# DebugUSB.net
KiCad netlist of a schematic drawn in Altium Designer
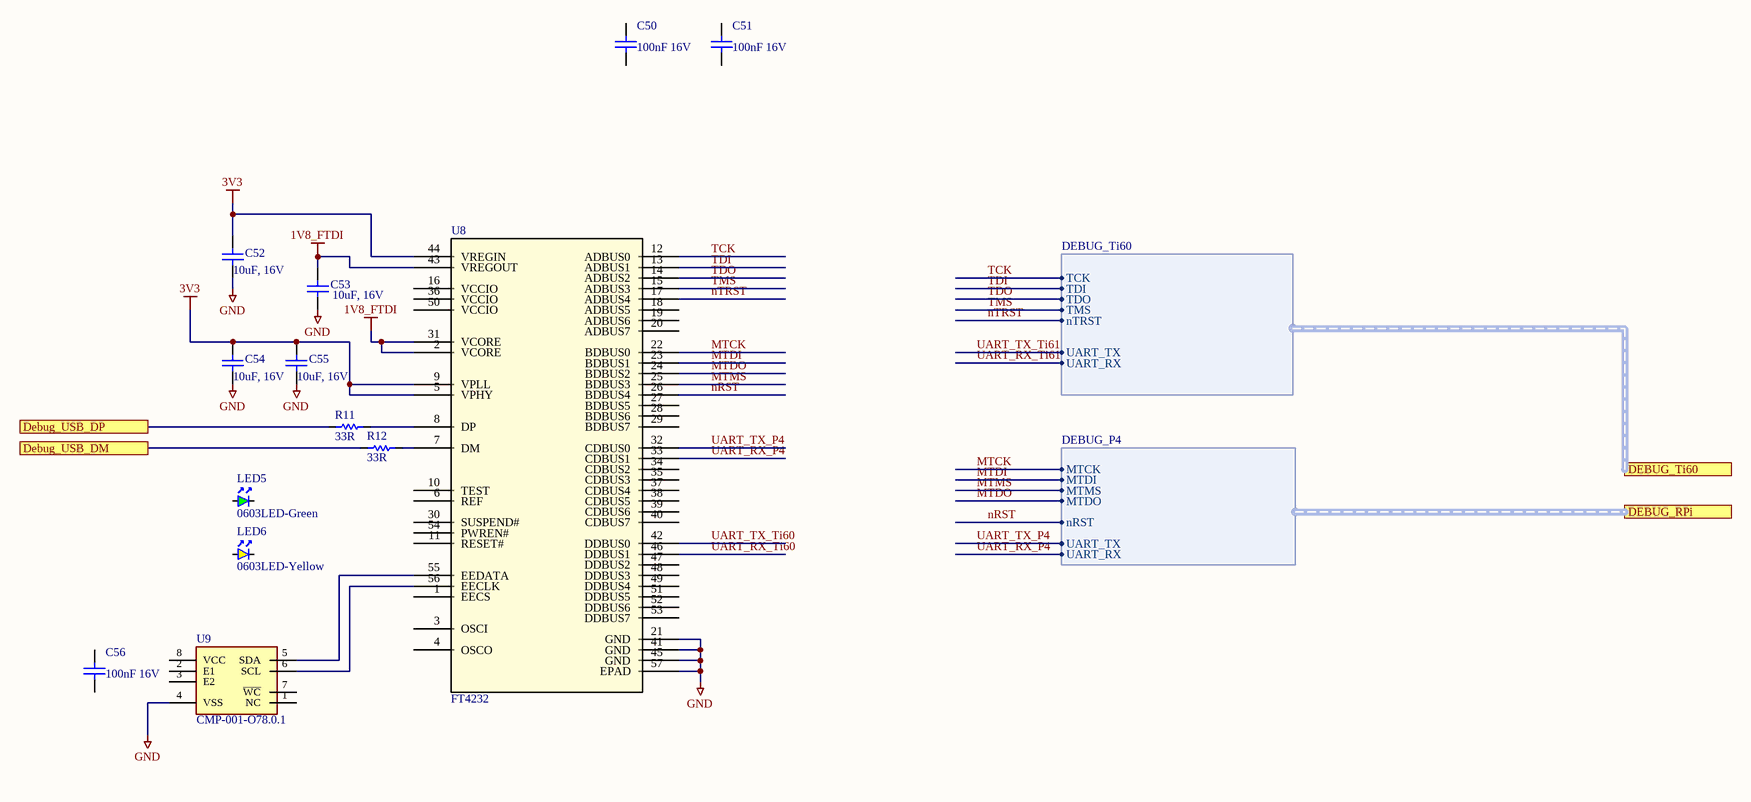
[diagram p0: DebugUSB.SchDoc]

(export (version "E")
  (design (tool "Eeschema 10.0.6"))
  (components
    (comp (ref "C50") (value "100nF 16V") (footprint "0402") (libsource (lib "Revolve NTNU") (part "CAP")))
    (comp (ref "C51") (value "100nF 16V") (footprint "0402") (libsource (lib "Revolve NTNU") (part "CAP")))
    (comp (ref "C52")
      (value "10uF, 16V")
      (footprint "0603 Capacitor")
      (description "10uF, 16V, 20%, X5R, 0603")
      (libsource (lib "Revolve NTNU") (part "CAP"))
    )
    (comp (ref "C53")
      (value "10uF, 16V")
      (footprint "0603 Capacitor")
      (description "10uF, 16V, 20%, X5R, 0603")
      (libsource (lib "Revolve NTNU") (part "CAP"))
    )
    (comp (ref "C54")
      (value "10uF, 16V")
      (footprint "0603 Capacitor")
      (description "10uF, 16V, 20%, X5R, 0603")
      (libsource (lib "Revolve NTNU") (part "CAP"))
    )
    (comp (ref "C55")
      (value "10uF, 16V")
      (footprint "0603 Capacitor")
      (description "10uF, 16V, 20%, X5R, 0603")
      (libsource (lib "Revolve NTNU") (part "CAP"))
    )
    (comp (ref "C56") (value "100nF 16V") (footprint "0402") (libsource (lib "Revolve NTNU") (part "CAP")))
    (comp (ref "LED5")
      (value "0603LED-Green")
      (footprint "LED-0603-RED")
      (description "SMD LED 0603, Green")
      (libsource (lib "Revolve NTNU") (part "LED"))
    )
    (comp (ref "LED6")
      (value "0603LED-Yellow")
      (footprint "LED-0603-RED")
      (description "SMD LED 0603, Yellow")
      (libsource (lib "Revolve NTNU") (part "LED"))
    )
    (comp (ref "R11")
      (value "33R")
      (footprint "0603 Resistor")
      (description "33R, 1%, 1/10W, 0603")
      (fields (field (name "TOLERANCE") "1%") (field (name "MANUFACTURER") "Panasonic"))
      (libsource (lib "Revolve NTNU") (part "Resistor"))
    )
    (comp (ref "R12")
      (value "33R")
      (footprint "0603 Resistor")
      (description "33R, 1%, 1/10W, 0603")
      (fields (field (name "TOLERANCE") "1%") (field (name "MANUFACTURER") "Panasonic"))
      (libsource (lib "Revolve NTNU") (part "Resistor"))
    )
    (comp (ref "U8")
      (value "FT4232")
      (footprint "VQFN-56Y856_FTD-M")
      (description "Usb Hi-speed to Quad Channel Serial UART/JTAG/SPI/I2C IC, QFN-56")
      (libsource (lib "Eirik Silnes") (part "FT4232H-56Q-REEL"))
    )
    (comp (ref "U9")
      (value "CMP-001-O78.0.1")
      (footprint "M24C04-DRMN3TP_K-Footprint-1")
      (description "IC EEPROM 4KBIT I2C 1MHZ 8SOIC")
      (fields
        (field (name "MANUFACTURER PART NUMBER") "M24C04-DRMN3TP/K")
        (field (name "MANUFACTURER") "STMicroelectronics")
      )
      (libsource (lib "Eirik Silnes") (part "CMP-001-O78.0.1"))
    )
  )
  (nets
    (net (code "3") (name "/Debug_USB_DM") (class "Default")
      (node (ref "R12") (pin "1") (pinfunction "1_1") (pintype "passive"))
    )
    (net (code "4") (name "/Debug_USB_DP") (class "Default")
      (node (ref "R11") (pin "1") (pinfunction "1_1") (pintype "passive"))
    )
    (net (code "5") (name "/MTCK") (class "Default")
      (node (ref "U8") (pin "22") (pinfunction "BDBUS0_22") (pintype "passive"))
    )
    (net (code "6") (name "/MTDI") (class "Default")
      (node (ref "U8") (pin "23") (pinfunction "BDBUS1_23") (pintype "passive"))
    )
    (net (code "7") (name "/MTDO") (class "Default")
      (node (ref "U8") (pin "24") (pinfunction "BDBUS2_24") (pintype "passive"))
    )
    (net (code "8") (name "/MTMS") (class "Default")
      (node (ref "U8") (pin "25") (pinfunction "BDBUS3_25") (pintype "passive"))
    )
    (net (code "9") (name "/TCK") (class "Default")
      (node (ref "U8") (pin "12") (pinfunction "ADBUS0_12") (pintype "passive"))
    )
    (net (code "10") (name "/TDI") (class "Default")
      (node (ref "U8") (pin "13") (pinfunction "ADBUS1_13") (pintype "passive"))
    )
    (net (code "11") (name "/TDO") (class "Default")
      (node (ref "U8") (pin "14") (pinfunction "ADBUS2_14") (pintype "passive"))
    )
    (net (code "12") (name "/TMS") (class "Default")
      (node (ref "U8") (pin "15") (pinfunction "ADBUS3_15") (pintype "passive"))
    )
    (net (code "13") (name "/UART_RX_P4") (class "Default")
      (node (ref "U8") (pin "33") (pinfunction "CDBUS1_33") (pintype "passive"))
    )
    (net (code "14") (name "/UART_RX_Ti60") (class "Default")
      (node (ref "U8") (pin "46") (pinfunction "DDBUS1_46") (pintype "passive"))
    )
    (net (code "16") (name "/UART_TX_P4") (class "Default")
      (node (ref "U8") (pin "32") (pinfunction "CDBUS0_32") (pintype "passive"))
    )
    (net (code "17") (name "/UART_TX_Ti60") (class "Default")
      (node (ref "U8") (pin "42") (pinfunction "DDBUS0_42") (pintype "passive"))
    )
    (net (code "19") (name "/nRST") (class "Default")
      (node (ref "U8") (pin "26") (pinfunction "BDBUS4_26") (pintype "passive"))
    )
    (net (code "20") (name "/nTRST") (class "Default")
      (node (ref "U8") (pin "17") (pinfunction "ADBUS4_17") (pintype "passive"))
    )
    (net (code "23") (name "1V8_FTDI") (class "Default")
      (node (ref "C53") (pin "2") (pinfunction "2_2") (pintype "passive"))
      (node (ref "U8") (pin "2") (pinfunction "VCORE_2") (pintype "passive"))
      (node (ref "U8") (pin "31") (pinfunction "VCORE_31") (pintype "passive"))
      (node (ref "U8") (pin "43") (pinfunction "VREGOUT_43") (pintype "passive"))
    )
    (net (code "24") (name "3V3") (class "Default")
      (node (ref "C52") (pin "2") (pinfunction "2_2") (pintype "passive"))
      (node (ref "C54") (pin "2") (pinfunction "2_2") (pintype "passive"))
      (node (ref "C55") (pin "2") (pinfunction "2_2") (pintype "passive"))
      (node (ref "U8") (pin "44") (pinfunction "VREGIN_44") (pintype "passive"))
      (node (ref "U8") (pin "5") (pinfunction "VPHY_5") (pintype "passive"))
      (node (ref "U8") (pin "9") (pinfunction "VPLL_9") (pintype "passive"))
    )
    (net (code "25") (name "GND") (class "Default")
      (node (ref "C52") (pin "1") (pinfunction "1_1") (pintype "passive"))
      (node (ref "C53") (pin "1") (pinfunction "1_1") (pintype "passive"))
      (node (ref "C54") (pin "1") (pinfunction "1_1") (pintype "passive"))
      (node (ref "C55") (pin "1") (pinfunction "1_1") (pintype "passive"))
      (node (ref "U8") (pin "21") (pinfunction "GND_21") (pintype "passive"))
      (node (ref "U8") (pin "41") (pinfunction "GND_41") (pintype "passive"))
      (node (ref "U8") (pin "45") (pinfunction "GND_45") (pintype "passive"))
      (node (ref "U8") (pin "57") (pinfunction "EPAD_57") (pintype "passive"))
      (node (ref "U9") (pin "4") (pinfunction "VSS_4") (pintype "passive"))
    )
    (net (code "26") (name "Net-(U8-DM)") (class "Default")
      (node (ref "R12") (pin "2") (pinfunction "2_2") (pintype "passive"))
      (node (ref "U8") (pin "7") (pinfunction "DM_7") (pintype "passive"))
    )
    (net (code "27") (name "Net-(U8-DP)") (class "Default")
      (node (ref "R11") (pin "2") (pinfunction "2_2") (pintype "passive"))
      (node (ref "U8") (pin "8") (pinfunction "DP_8") (pintype "passive"))
    )
    (net (code "28") (name "Net-(U8-EECLK)") (class "Default")
      (node (ref "U8") (pin "56") (pinfunction "EECLK_56") (pintype "passive"))
      (node (ref "U9") (pin "6") (pinfunction "SCL_6") (pintype "passive"))
    )
    (net (code "29") (name "Net-(U8-EEDATA)") (class "Default")
      (node (ref "U8") (pin "55") (pinfunction "EEDATA_55") (pintype "passive"))
      (node (ref "U9") (pin "5") (pinfunction "SDA_5") (pintype "passive"))
    )
    (net (code "30") (name "unconnected-(C50-Pad1)") (class "Default")
      (node (ref "C50") (pin "1") (pinfunction "1_1") (pintype "passive"))
    )
    (net (code "31") (name "unconnected-(C50-Pad2)") (class "Default")
      (node (ref "C50") (pin "2") (pinfunction "2_2") (pintype "passive"))
    )
    (net (code "32") (name "unconnected-(C51-Pad1)") (class "Default")
      (node (ref "C51") (pin "1") (pinfunction "1_1") (pintype "passive"))
    )
    (net (code "33") (name "unconnected-(C51-Pad2)") (class "Default")
      (node (ref "C51") (pin "2") (pinfunction "2_2") (pintype "passive"))
    )
    (net (code "34") (name "unconnected-(C56-Pad1)") (class "Default")
      (node (ref "C56") (pin "1") (pinfunction "1_1") (pintype "passive"))
    )
    (net (code "35") (name "unconnected-(C56-Pad2)") (class "Default")
      (node (ref "C56") (pin "2") (pinfunction "2_2") (pintype "passive"))
    )
    (net (code "36") (name "unconnected-(LED5-A-Pad1)") (class "Default")
      (node (ref "LED5") (pin "1") (pinfunction "A_1") (pintype "passive"))
    )
    (net (code "37") (name "unconnected-(LED5-K-Pad2)") (class "Default")
      (node (ref "LED5") (pin "2") (pinfunction "K_2") (pintype "passive"))
    )
    (net (code "38") (name "unconnected-(LED6-A-Pad1)") (class "Default")
      (node (ref "LED6") (pin "1") (pinfunction "A_1") (pintype "passive"))
    )
    (net (code "39") (name "unconnected-(LED6-K-Pad2)") (class "Default")
      (node (ref "LED6") (pin "2") (pinfunction "K_2") (pintype "passive"))
    )
    (net (code "40") (name "unconnected-(U8-ADBUS5-Pad18)") (class "Default")
      (node (ref "U8") (pin "18") (pinfunction "ADBUS5_18") (pintype "passive"))
    )
    (net (code "41") (name "unconnected-(U8-ADBUS6-Pad19)") (class "Default")
      (node (ref "U8") (pin "19") (pinfunction "ADBUS6_19") (pintype "passive"))
    )
    (net (code "42") (name "unconnected-(U8-ADBUS7-Pad20)") (class "Default")
      (node (ref "U8") (pin "20") (pinfunction "ADBUS7_20") (pintype "passive"))
    )
    (net (code "43") (name "unconnected-(U8-BDBUS5-Pad27)") (class "Default")
      (node (ref "U8") (pin "27") (pinfunction "BDBUS5_27") (pintype "passive"))
    )
    (net (code "44") (name "unconnected-(U8-BDBUS6-Pad28)") (class "Default")
      (node (ref "U8") (pin "28") (pinfunction "BDBUS6_28") (pintype "passive"))
    )
    (net (code "45") (name "unconnected-(U8-BDBUS7-Pad29)") (class "Default")
      (node (ref "U8") (pin "29") (pinfunction "BDBUS7_29") (pintype "passive"))
    )
    (net (code "46") (name "unconnected-(U8-CDBUS2-Pad34)") (class "Default")
      (node (ref "U8") (pin "34") (pinfunction "CDBUS2_34") (pintype "passive"))
    )
    (net (code "47") (name "unconnected-(U8-CDBUS3-Pad35)") (class "Default")
      (node (ref "U8") (pin "35") (pinfunction "CDBUS3_35") (pintype "passive"))
    )
    (net (code "48") (name "unconnected-(U8-CDBUS4-Pad37)") (class "Default")
      (node (ref "U8") (pin "37") (pinfunction "CDBUS4_37") (pintype "passive"))
    )
    (net (code "49") (name "unconnected-(U8-CDBUS5-Pad38)") (class "Default")
      (node (ref "U8") (pin "38") (pinfunction "CDBUS5_38") (pintype "passive"))
    )
    (net (code "50") (name "unconnected-(U8-CDBUS6-Pad39)") (class "Default")
      (node (ref "U8") (pin "39") (pinfunction "CDBUS6_39") (pintype "passive"))
    )
    (net (code "51") (name "unconnected-(U8-CDBUS7-Pad40)") (class "Default")
      (node (ref "U8") (pin "40") (pinfunction "CDBUS7_40") (pintype "passive"))
    )
    (net (code "52") (name "unconnected-(U8-DDBUS2-Pad47)") (class "Default")
      (node (ref "U8") (pin "47") (pinfunction "DDBUS2_47") (pintype "passive"))
    )
    (net (code "53") (name "unconnected-(U8-DDBUS3-Pad48)") (class "Default")
      (node (ref "U8") (pin "48") (pinfunction "DDBUS3_48") (pintype "passive"))
    )
    (net (code "54") (name "unconnected-(U8-DDBUS4-Pad49)") (class "Default")
      (node (ref "U8") (pin "49") (pinfunction "DDBUS4_49") (pintype "passive"))
    )
    (net (code "55") (name "unconnected-(U8-DDBUS5-Pad51)") (class "Default")
      (node (ref "U8") (pin "51") (pinfunction "DDBUS5_51") (pintype "passive"))
    )
    (net (code "56") (name "unconnected-(U8-DDBUS6-Pad52)") (class "Default")
      (node (ref "U8") (pin "52") (pinfunction "DDBUS6_52") (pintype "passive"))
    )
    (net (code "57") (name "unconnected-(U8-DDBUS7-Pad53)") (class "Default")
      (node (ref "U8") (pin "53") (pinfunction "DDBUS7_53") (pintype "passive"))
    )
    (net (code "58") (name "unconnected-(U8-EECS-Pad1)") (class "Default")
      (node (ref "U8") (pin "1") (pinfunction "EECS_1") (pintype "passive"))
    )
    (net (code "59") (name "unconnected-(U8-OSCI-Pad3)") (class "Default")
      (node (ref "U8") (pin "3") (pinfunction "OSCI_3") (pintype "passive"))
    )
    (net (code "60") (name "unconnected-(U8-OSCO-Pad4)") (class "Default")
      (node (ref "U8") (pin "4") (pinfunction "OSCO_4") (pintype "passive"))
    )
    (net (code "61") (name "unconnected-(U8-PWREN#-Pad54)") (class "Default")
      (node (ref "U8") (pin "54") (pinfunction "PWREN#_54") (pintype "passive"))
    )
    (net (code "62") (name "unconnected-(U8-REF-Pad6)") (class "Default")
      (node (ref "U8") (pin "6") (pinfunction "REF_6") (pintype "passive"))
    )
    (net (code "63") (name "unconnected-(U8-RESET#-Pad11)") (class "Default")
      (node (ref "U8") (pin "11") (pinfunction "RESET#_11") (pintype "passive"))
    )
    (net (code "64") (name "unconnected-(U8-SUSPEND#-Pad30)") (class "Default")
      (node (ref "U8") (pin "30") (pinfunction "SUSPEND#_30") (pintype "passive"))
    )
    (net (code "65") (name "unconnected-(U8-TEST-Pad10)") (class "Default")
      (node (ref "U8") (pin "10") (pinfunction "TEST_10") (pintype "passive"))
    )
    (net (code "66") (name "unconnected-(U8-VCCIO-Pad16)") (class "Default")
      (node (ref "U8") (pin "16") (pinfunction "VCCIO_16") (pintype "passive"))
    )
    (net (code "67") (name "unconnected-(U8-VCCIO-Pad36)") (class "Default")
      (node (ref "U8") (pin "36") (pinfunction "VCCIO_36") (pintype "passive"))
    )
    (net (code "68") (name "unconnected-(U8-VCCIO-Pad50)") (class "Default")
      (node (ref "U8") (pin "50") (pinfunction "VCCIO_50") (pintype "passive"))
    )
    (net (code "69") (name "unconnected-(U9-E1-Pad2)") (class "Default")
      (node (ref "U9") (pin "2") (pinfunction "E1_2") (pintype "passive"))
    )
    (net (code "70") (name "unconnected-(U9-E2-Pad3)") (class "Default")
      (node (ref "U9") (pin "3") (pinfunction "E2_3") (pintype "passive"))
    )
    (net (code "71") (name "unconnected-(U9-NC-Pad1)") (class "Default")
      (node (ref "U9") (pin "1") (pinfunction "NC_1") (pintype "passive"))
    )
    (net (code "72") (name "unconnected-(U9-VCC-Pad8)") (class "Default")
      (node (ref "U9") (pin "8") (pinfunction "VCC_8") (pintype "passive"))
    )
    (net (code "73") (name "unconnected-(U9-~{WC}-Pad7)") (class "Default")
      (node (ref "U9") (pin "7") (pinfunction "~{WC}_7") (pintype "passive"))
    )
  )
)
